# apa104-breakout.net
KiCad netlist of a schematic drawn in EAGLE
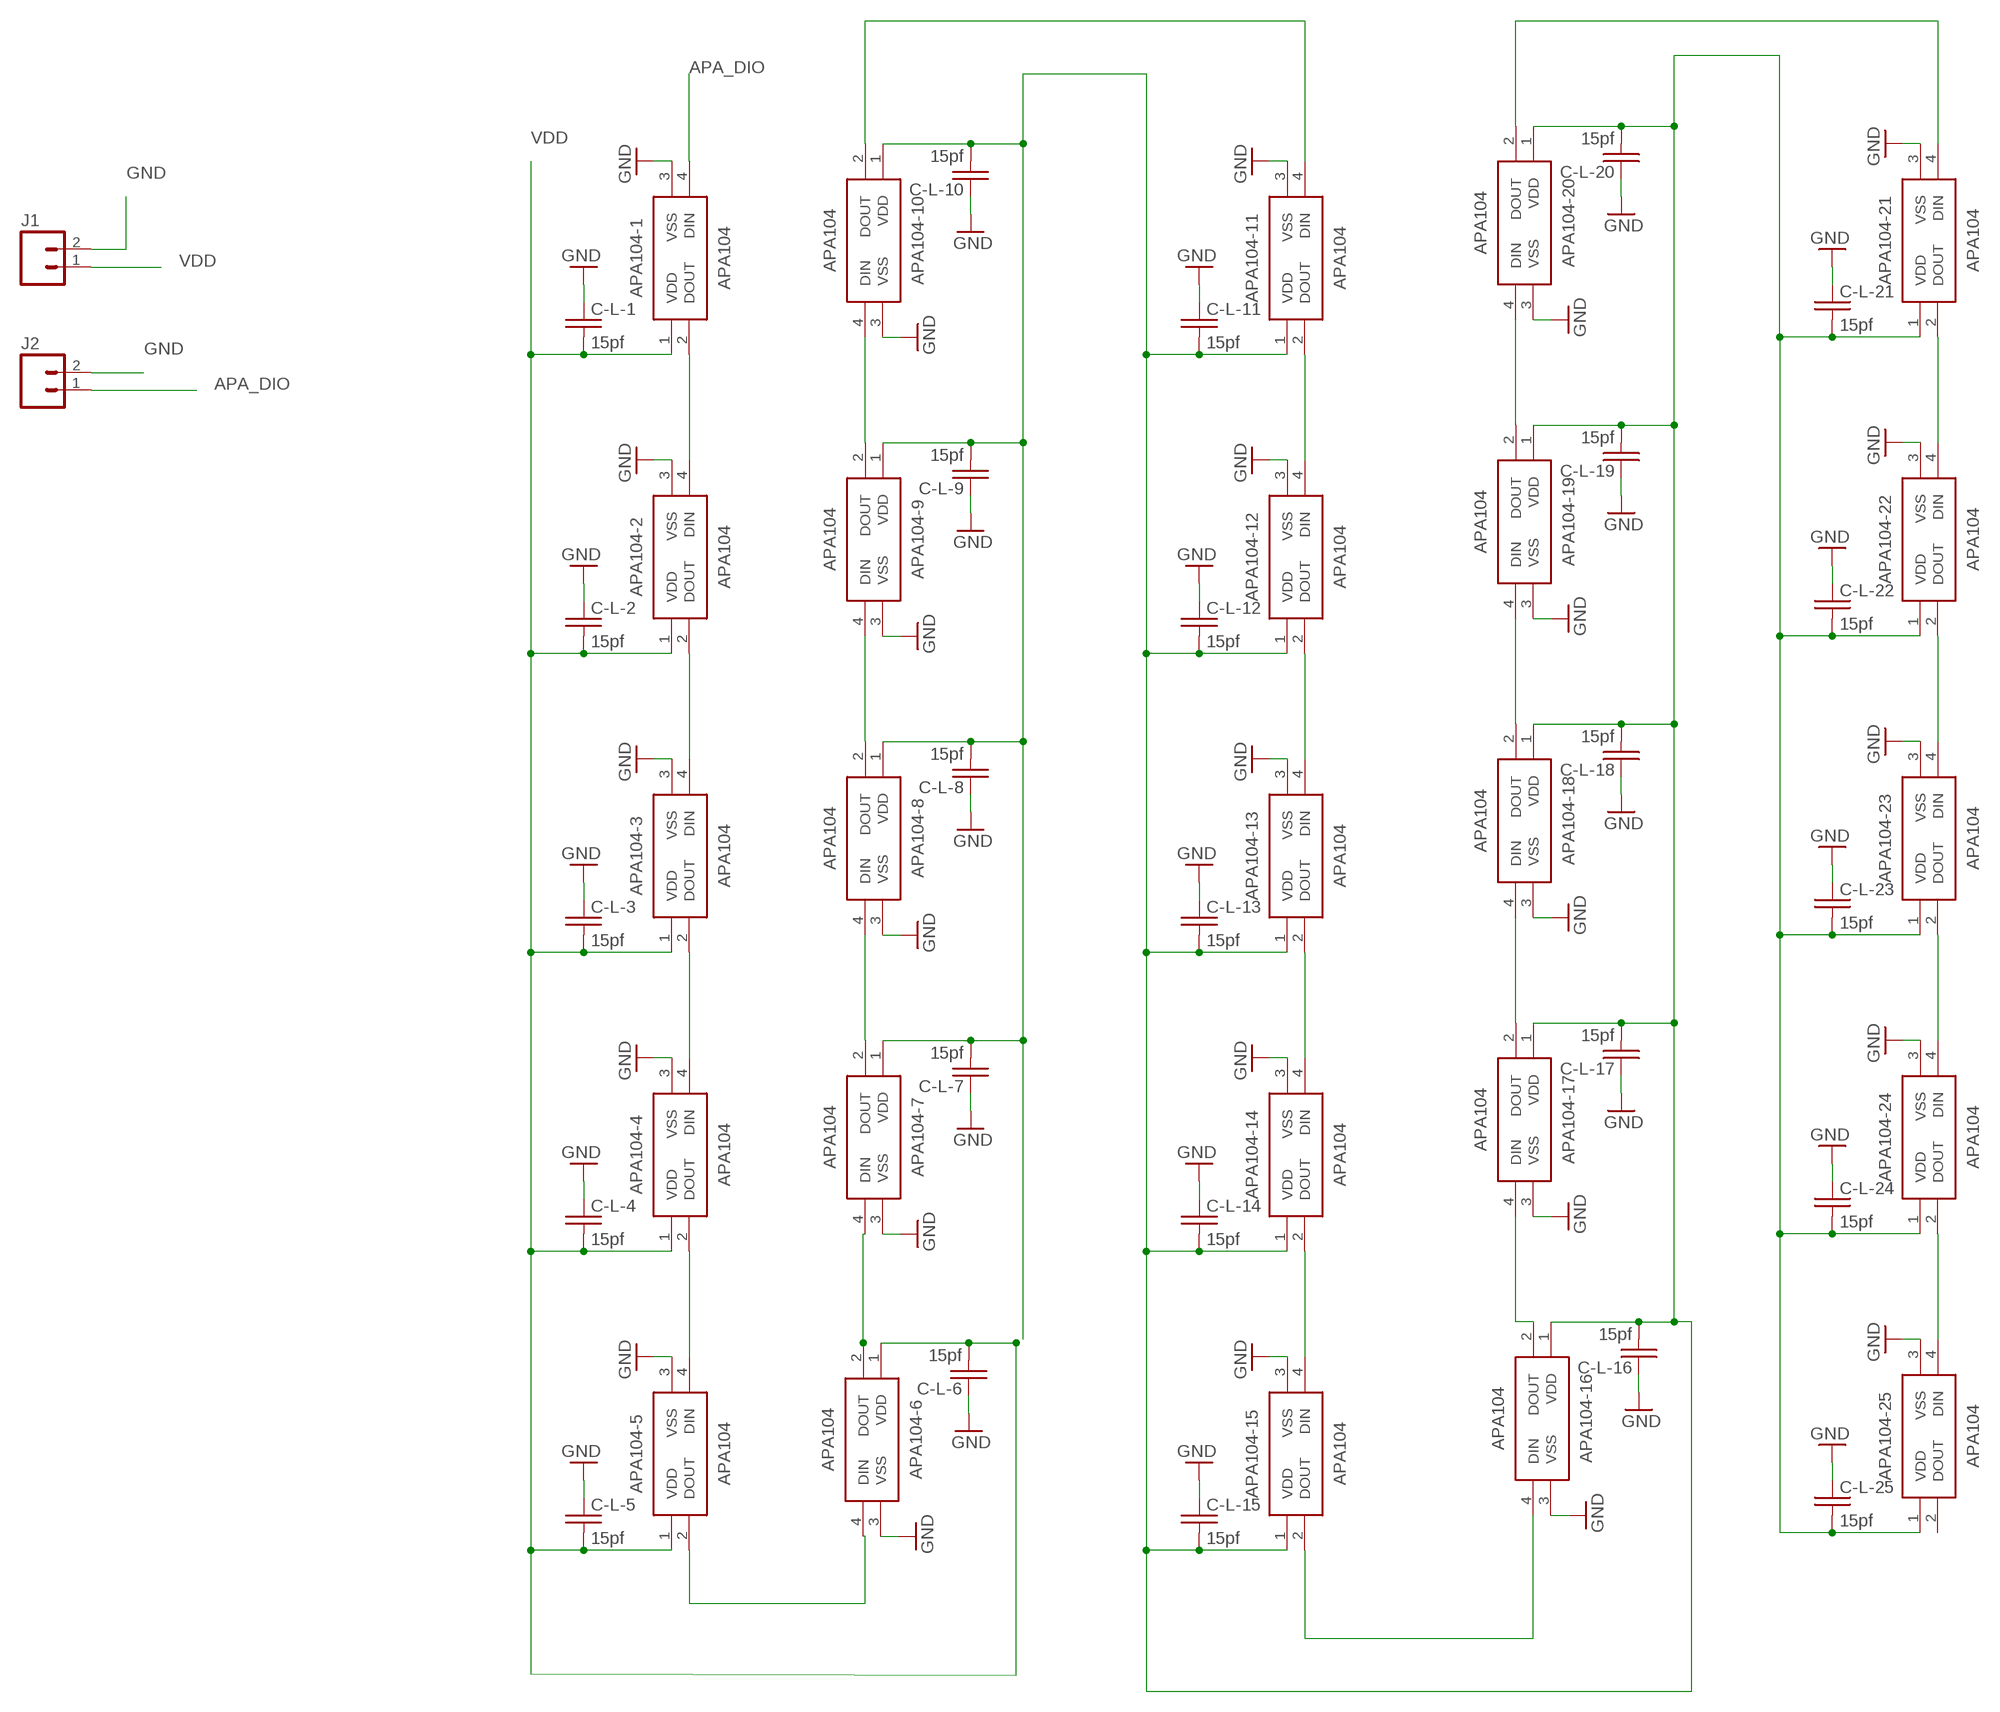
[diagram p0: schematic, sheet 1]

(export (version "E")
  (design (tool "Eeschema 10.0.6"))
  (components
    (comp (ref "APA104-1")
      (value "APA104")
      (footprint "eagle-import:APA104")
      (libsource (lib "eagle-import") (part "APA104"))
    )
    (comp (ref "APA104-2")
      (value "APA104")
      (footprint "eagle-import:APA104")
      (libsource (lib "eagle-import") (part "APA104"))
    )
    (comp (ref "APA104-3")
      (value "APA104")
      (footprint "eagle-import:APA104")
      (libsource (lib "eagle-import") (part "APA104"))
    )
    (comp (ref "APA104-4")
      (value "APA104")
      (footprint "eagle-import:APA104")
      (libsource (lib "eagle-import") (part "APA104"))
    )
    (comp (ref "APA104-5")
      (value "APA104")
      (footprint "eagle-import:APA104")
      (libsource (lib "eagle-import") (part "APA104"))
    )
    (comp (ref "APA104-6")
      (value "APA104")
      (footprint "eagle-import:APA104")
      (libsource (lib "eagle-import") (part "APA104"))
    )
    (comp (ref "APA104-7")
      (value "APA104")
      (footprint "eagle-import:APA104")
      (libsource (lib "eagle-import") (part "APA104"))
    )
    (comp (ref "APA104-8")
      (value "APA104")
      (footprint "eagle-import:APA104")
      (libsource (lib "eagle-import") (part "APA104"))
    )
    (comp (ref "APA104-9")
      (value "APA104")
      (footprint "eagle-import:APA104")
      (libsource (lib "eagle-import") (part "APA104"))
    )
    (comp (ref "APA104-10")
      (value "APA104")
      (footprint "eagle-import:APA104")
      (libsource (lib "eagle-import") (part "APA104"))
    )
    (comp (ref "APA104-11")
      (value "APA104")
      (footprint "eagle-import:APA104")
      (libsource (lib "eagle-import") (part "APA104"))
    )
    (comp (ref "APA104-12")
      (value "APA104")
      (footprint "eagle-import:APA104")
      (libsource (lib "eagle-import") (part "APA104"))
    )
    (comp (ref "APA104-13")
      (value "APA104")
      (footprint "eagle-import:APA104")
      (libsource (lib "eagle-import") (part "APA104"))
    )
    (comp (ref "APA104-14")
      (value "APA104")
      (footprint "eagle-import:APA104")
      (libsource (lib "eagle-import") (part "APA104"))
    )
    (comp (ref "APA104-15")
      (value "APA104")
      (footprint "eagle-import:APA104")
      (libsource (lib "eagle-import") (part "APA104"))
    )
    (comp (ref "APA104-16")
      (value "APA104")
      (footprint "eagle-import:APA104")
      (libsource (lib "eagle-import") (part "APA104"))
    )
    (comp (ref "APA104-17")
      (value "APA104")
      (footprint "eagle-import:APA104")
      (libsource (lib "eagle-import") (part "APA104"))
    )
    (comp (ref "APA104-18")
      (value "APA104")
      (footprint "eagle-import:APA104")
      (libsource (lib "eagle-import") (part "APA104"))
    )
    (comp (ref "APA104-19")
      (value "APA104")
      (footprint "eagle-import:APA104")
      (libsource (lib "eagle-import") (part "APA104"))
    )
    (comp (ref "APA104-20")
      (value "APA104")
      (footprint "eagle-import:APA104")
      (libsource (lib "eagle-import") (part "APA104"))
    )
    (comp (ref "APA104-21")
      (value "APA104")
      (footprint "eagle-import:APA104")
      (libsource (lib "eagle-import") (part "APA104"))
    )
    (comp (ref "APA104-22")
      (value "APA104")
      (footprint "eagle-import:APA104")
      (libsource (lib "eagle-import") (part "APA104"))
    )
    (comp (ref "APA104-23")
      (value "APA104")
      (footprint "eagle-import:APA104")
      (libsource (lib "eagle-import") (part "APA104"))
    )
    (comp (ref "APA104-24")
      (value "APA104")
      (footprint "eagle-import:APA104")
      (libsource (lib "eagle-import") (part "APA104"))
    )
    (comp (ref "APA104-25")
      (value "APA104")
      (footprint "eagle-import:APA104")
      (libsource (lib "eagle-import") (part "APA104"))
    )
    (comp (ref "C-L-1")
      (value "15pf")
      (footprint "eagle-import:C0805-VOLTA")
      (libsource (lib "eagle-import") (part "C-USC0805-VOLTERA"))
    )
    (comp (ref "C-L-2")
      (value "15pf")
      (footprint "eagle-import:C0805-VOLTA")
      (libsource (lib "eagle-import") (part "C-USC0805-VOLTERA"))
    )
    (comp (ref "C-L-3")
      (value "15pf")
      (footprint "eagle-import:C0805-VOLTA")
      (libsource (lib "eagle-import") (part "C-USC0805-VOLTERA"))
    )
    (comp (ref "C-L-4")
      (value "15pf")
      (footprint "eagle-import:C0805-VOLTA")
      (libsource (lib "eagle-import") (part "C-USC0805-VOLTERA"))
    )
    (comp (ref "C-L-5")
      (value "15pf")
      (footprint "eagle-import:C0805-VOLTA")
      (libsource (lib "eagle-import") (part "C-USC0805-VOLTERA"))
    )
    (comp (ref "C-L-6")
      (value "15pf")
      (footprint "eagle-import:C0805-VOLTA")
      (libsource (lib "eagle-import") (part "C-USC0805-VOLTERA"))
    )
    (comp (ref "C-L-7")
      (value "15pf")
      (footprint "eagle-import:C0805-VOLTA")
      (libsource (lib "eagle-import") (part "C-USC0805-VOLTERA"))
    )
    (comp (ref "C-L-8")
      (value "15pf")
      (footprint "eagle-import:C0805-VOLTA")
      (libsource (lib "eagle-import") (part "C-USC0805-VOLTERA"))
    )
    (comp (ref "C-L-9")
      (value "15pf")
      (footprint "eagle-import:C0805-VOLTA")
      (libsource (lib "eagle-import") (part "C-USC0805-VOLTERA"))
    )
    (comp (ref "C-L-10")
      (value "15pf")
      (footprint "eagle-import:C0805-VOLTA")
      (libsource (lib "eagle-import") (part "C-USC0805-VOLTERA"))
    )
    (comp (ref "C-L-11")
      (value "15pf")
      (footprint "eagle-import:C0805-VOLTA")
      (libsource (lib "eagle-import") (part "C-USC0805-VOLTERA"))
    )
    (comp (ref "C-L-12")
      (value "15pf")
      (footprint "eagle-import:C0805-VOLTA")
      (libsource (lib "eagle-import") (part "C-USC0805-VOLTERA"))
    )
    (comp (ref "C-L-13")
      (value "15pf")
      (footprint "eagle-import:C0805-VOLTA")
      (libsource (lib "eagle-import") (part "C-USC0805-VOLTERA"))
    )
    (comp (ref "C-L-14")
      (value "15pf")
      (footprint "eagle-import:C0805-VOLTA")
      (libsource (lib "eagle-import") (part "C-USC0805-VOLTERA"))
    )
    (comp (ref "C-L-15")
      (value "15pf")
      (footprint "eagle-import:C0805-VOLTA")
      (libsource (lib "eagle-import") (part "C-USC0805-VOLTERA"))
    )
    (comp (ref "C-L-16")
      (value "15pf")
      (footprint "eagle-import:C0805-VOLTA")
      (libsource (lib "eagle-import") (part "C-USC0805-VOLTERA"))
    )
    (comp (ref "C-L-17")
      (value "15pf")
      (footprint "eagle-import:C0805-VOLTA")
      (libsource (lib "eagle-import") (part "C-USC0805-VOLTERA"))
    )
    (comp (ref "C-L-18")
      (value "15pf")
      (footprint "eagle-import:C0805-VOLTA")
      (libsource (lib "eagle-import") (part "C-USC0805-VOLTERA"))
    )
    (comp (ref "C-L-19")
      (value "15pf")
      (footprint "eagle-import:C0805-VOLTA")
      (libsource (lib "eagle-import") (part "C-USC0805-VOLTERA"))
    )
    (comp (ref "C-L-20")
      (value "15pf")
      (footprint "eagle-import:C0805-VOLTA")
      (libsource (lib "eagle-import") (part "C-USC0805-VOLTERA"))
    )
    (comp (ref "C-L-21")
      (value "15pf")
      (footprint "eagle-import:C0805-VOLTA")
      (libsource (lib "eagle-import") (part "C-USC0805-VOLTERA"))
    )
    (comp (ref "C-L-22")
      (value "15pf")
      (footprint "eagle-import:C0805-VOLTA")
      (libsource (lib "eagle-import") (part "C-USC0805-VOLTERA"))
    )
    (comp (ref "C-L-23")
      (value "15pf")
      (footprint "eagle-import:C0805-VOLTA")
      (libsource (lib "eagle-import") (part "C-USC0805-VOLTERA"))
    )
    (comp (ref "C-L-24")
      (value "15pf")
      (footprint "eagle-import:C0805-VOLTA")
      (libsource (lib "eagle-import") (part "C-USC0805-VOLTERA"))
    )
    (comp (ref "C-L-25")
      (value "15pf")
      (footprint "eagle-import:C0805-VOLTA")
      (libsource (lib "eagle-import") (part "C-USC0805-VOLTERA"))
    )
    (comp (ref "J1")
      (value "M02PTH")
      (footprint "eagle-import:1X02")
      (libsource (lib "eagle-import") (part "M02PTH"))
    )
    (comp (ref "J2")
      (value "M02PTH")
      (footprint "eagle-import:1X02")
      (libsource (lib "eagle-import") (part "M02PTH"))
    )
  )
  (nets
    (net (code "1") (name "/APA_DIO") (class "Default")
      (node (ref "APA104-1") (pin "4") (pinfunction "DIN_4") (pintype "input"))
      (node (ref "J2") (pin "1") (pinfunction "1_1") (pintype "passive"))
    )
    (net (code "2") (name "/VDD") (class "Default")
      (node (ref "APA104-1") (pin "1") (pinfunction "VDD_1") (pintype "power_in"))
      (node (ref "APA104-10") (pin "1") (pinfunction "VDD_1") (pintype "power_in"))
      (node (ref "APA104-11") (pin "1") (pinfunction "VDD_1") (pintype "power_in"))
      (node (ref "APA104-12") (pin "1") (pinfunction "VDD_1") (pintype "power_in"))
      (node (ref "APA104-13") (pin "1") (pinfunction "VDD_1") (pintype "power_in"))
      (node (ref "APA104-14") (pin "1") (pinfunction "VDD_1") (pintype "power_in"))
      (node (ref "APA104-15") (pin "1") (pinfunction "VDD_1") (pintype "power_in"))
      (node (ref "APA104-16") (pin "1") (pinfunction "VDD_1") (pintype "power_in"))
      (node (ref "APA104-17") (pin "1") (pinfunction "VDD_1") (pintype "power_in"))
      (node (ref "APA104-18") (pin "1") (pinfunction "VDD_1") (pintype "power_in"))
      (node (ref "APA104-19") (pin "1") (pinfunction "VDD_1") (pintype "power_in"))
      (node (ref "APA104-2") (pin "1") (pinfunction "VDD_1") (pintype "power_in"))
      (node (ref "APA104-20") (pin "1") (pinfunction "VDD_1") (pintype "power_in"))
      (node (ref "APA104-21") (pin "1") (pinfunction "VDD_1") (pintype "power_in"))
      (node (ref "APA104-22") (pin "1") (pinfunction "VDD_1") (pintype "power_in"))
      (node (ref "APA104-23") (pin "1") (pinfunction "VDD_1") (pintype "power_in"))
      (node (ref "APA104-24") (pin "1") (pinfunction "VDD_1") (pintype "power_in"))
      (node (ref "APA104-25") (pin "1") (pinfunction "VDD_1") (pintype "power_in"))
      (node (ref "APA104-3") (pin "1") (pinfunction "VDD_1") (pintype "power_in"))
      (node (ref "APA104-4") (pin "1") (pinfunction "VDD_1") (pintype "power_in"))
      (node (ref "APA104-5") (pin "1") (pinfunction "VDD_1") (pintype "power_in"))
      (node (ref "APA104-6") (pin "1") (pinfunction "VDD_1") (pintype "power_in"))
      (node (ref "APA104-7") (pin "1") (pinfunction "VDD_1") (pintype "power_in"))
      (node (ref "APA104-8") (pin "1") (pinfunction "VDD_1") (pintype "power_in"))
      (node (ref "APA104-9") (pin "1") (pinfunction "VDD_1") (pintype "power_in"))
      (node (ref "C-L-1") (pin "2") (pinfunction "2_2") (pintype "passive"))
      (node (ref "C-L-10") (pin "2") (pinfunction "2_2") (pintype "passive"))
      (node (ref "C-L-11") (pin "2") (pinfunction "2_2") (pintype "passive"))
      (node (ref "C-L-12") (pin "2") (pinfunction "2_2") (pintype "passive"))
      (node (ref "C-L-13") (pin "2") (pinfunction "2_2") (pintype "passive"))
      (node (ref "C-L-14") (pin "2") (pinfunction "2_2") (pintype "passive"))
      (node (ref "C-L-15") (pin "2") (pinfunction "2_2") (pintype "passive"))
      (node (ref "C-L-16") (pin "2") (pinfunction "2_2") (pintype "passive"))
      (node (ref "C-L-17") (pin "2") (pinfunction "2_2") (pintype "passive"))
      (node (ref "C-L-18") (pin "2") (pinfunction "2_2") (pintype "passive"))
      (node (ref "C-L-19") (pin "2") (pinfunction "2_2") (pintype "passive"))
      (node (ref "C-L-2") (pin "2") (pinfunction "2_2") (pintype "passive"))
      (node (ref "C-L-20") (pin "2") (pinfunction "2_2") (pintype "passive"))
      (node (ref "C-L-21") (pin "2") (pinfunction "2_2") (pintype "passive"))
      (node (ref "C-L-22") (pin "2") (pinfunction "2_2") (pintype "passive"))
      (node (ref "C-L-23") (pin "2") (pinfunction "2_2") (pintype "passive"))
      (node (ref "C-L-24") (pin "2") (pinfunction "2_2") (pintype "passive"))
      (node (ref "C-L-25") (pin "2") (pinfunction "2_2") (pintype "passive"))
      (node (ref "C-L-3") (pin "2") (pinfunction "2_2") (pintype "passive"))
      (node (ref "C-L-4") (pin "2") (pinfunction "2_2") (pintype "passive"))
      (node (ref "C-L-5") (pin "2") (pinfunction "2_2") (pintype "passive"))
      (node (ref "C-L-6") (pin "2") (pinfunction "2_2") (pintype "passive"))
      (node (ref "C-L-7") (pin "2") (pinfunction "2_2") (pintype "passive"))
      (node (ref "C-L-8") (pin "2") (pinfunction "2_2") (pintype "passive"))
      (node (ref "C-L-9") (pin "2") (pinfunction "2_2") (pintype "passive"))
      (node (ref "J1") (pin "1") (pinfunction "1_1") (pintype "passive"))
    )
    (net (code "3") (name "GND") (class "Default")
      (node (ref "APA104-1") (pin "3") (pinfunction "VSS_3") (pintype "power_in"))
      (node (ref "APA104-10") (pin "3") (pinfunction "VSS_3") (pintype "power_in"))
      (node (ref "APA104-11") (pin "3") (pinfunction "VSS_3") (pintype "power_in"))
      (node (ref "APA104-12") (pin "3") (pinfunction "VSS_3") (pintype "power_in"))
      (node (ref "APA104-13") (pin "3") (pinfunction "VSS_3") (pintype "power_in"))
      (node (ref "APA104-14") (pin "3") (pinfunction "VSS_3") (pintype "power_in"))
      (node (ref "APA104-15") (pin "3") (pinfunction "VSS_3") (pintype "power_in"))
      (node (ref "APA104-16") (pin "3") (pinfunction "VSS_3") (pintype "power_in"))
      (node (ref "APA104-17") (pin "3") (pinfunction "VSS_3") (pintype "power_in"))
      (node (ref "APA104-18") (pin "3") (pinfunction "VSS_3") (pintype "power_in"))
      (node (ref "APA104-19") (pin "3") (pinfunction "VSS_3") (pintype "power_in"))
      (node (ref "APA104-2") (pin "3") (pinfunction "VSS_3") (pintype "power_in"))
      (node (ref "APA104-20") (pin "3") (pinfunction "VSS_3") (pintype "power_in"))
      (node (ref "APA104-21") (pin "3") (pinfunction "VSS_3") (pintype "power_in"))
      (node (ref "APA104-22") (pin "3") (pinfunction "VSS_3") (pintype "power_in"))
      (node (ref "APA104-23") (pin "3") (pinfunction "VSS_3") (pintype "power_in"))
      (node (ref "APA104-24") (pin "3") (pinfunction "VSS_3") (pintype "power_in"))
      (node (ref "APA104-25") (pin "3") (pinfunction "VSS_3") (pintype "power_in"))
      (node (ref "APA104-3") (pin "3") (pinfunction "VSS_3") (pintype "power_in"))
      (node (ref "APA104-4") (pin "3") (pinfunction "VSS_3") (pintype "power_in"))
      (node (ref "APA104-5") (pin "3") (pinfunction "VSS_3") (pintype "power_in"))
      (node (ref "APA104-6") (pin "3") (pinfunction "VSS_3") (pintype "power_in"))
      (node (ref "APA104-7") (pin "3") (pinfunction "VSS_3") (pintype "power_in"))
      (node (ref "APA104-8") (pin "3") (pinfunction "VSS_3") (pintype "power_in"))
      (node (ref "APA104-9") (pin "3") (pinfunction "VSS_3") (pintype "power_in"))
      (node (ref "C-L-1") (pin "1") (pinfunction "1_1") (pintype "passive"))
      (node (ref "C-L-10") (pin "1") (pinfunction "1_1") (pintype "passive"))
      (node (ref "C-L-11") (pin "1") (pinfunction "1_1") (pintype "passive"))
      (node (ref "C-L-12") (pin "1") (pinfunction "1_1") (pintype "passive"))
      (node (ref "C-L-13") (pin "1") (pinfunction "1_1") (pintype "passive"))
      (node (ref "C-L-14") (pin "1") (pinfunction "1_1") (pintype "passive"))
      (node (ref "C-L-15") (pin "1") (pinfunction "1_1") (pintype "passive"))
      (node (ref "C-L-16") (pin "1") (pinfunction "1_1") (pintype "passive"))
      (node (ref "C-L-17") (pin "1") (pinfunction "1_1") (pintype "passive"))
      (node (ref "C-L-18") (pin "1") (pinfunction "1_1") (pintype "passive"))
      (node (ref "C-L-19") (pin "1") (pinfunction "1_1") (pintype "passive"))
      (node (ref "C-L-2") (pin "1") (pinfunction "1_1") (pintype "passive"))
      (node (ref "C-L-20") (pin "1") (pinfunction "1_1") (pintype "passive"))
      (node (ref "C-L-21") (pin "1") (pinfunction "1_1") (pintype "passive"))
      (node (ref "C-L-22") (pin "1") (pinfunction "1_1") (pintype "passive"))
      (node (ref "C-L-23") (pin "1") (pinfunction "1_1") (pintype "passive"))
      (node (ref "C-L-24") (pin "1") (pinfunction "1_1") (pintype "passive"))
      (node (ref "C-L-25") (pin "1") (pinfunction "1_1") (pintype "passive"))
      (node (ref "C-L-3") (pin "1") (pinfunction "1_1") (pintype "passive"))
      (node (ref "C-L-4") (pin "1") (pinfunction "1_1") (pintype "passive"))
      (node (ref "C-L-5") (pin "1") (pinfunction "1_1") (pintype "passive"))
      (node (ref "C-L-6") (pin "1") (pinfunction "1_1") (pintype "passive"))
      (node (ref "C-L-7") (pin "1") (pinfunction "1_1") (pintype "passive"))
      (node (ref "C-L-8") (pin "1") (pinfunction "1_1") (pintype "passive"))
      (node (ref "C-L-9") (pin "1") (pinfunction "1_1") (pintype "passive"))
      (node (ref "J1") (pin "2") (pinfunction "2_2") (pintype "passive"))
      (node (ref "J2") (pin "2") (pinfunction "2_2") (pintype "passive"))
    )
    (net (code "4") (name "Net-(APA104-1-DOUT)") (class "Default")
      (node (ref "APA104-1") (pin "2") (pinfunction "DOUT_2") (pintype "output"))
      (node (ref "APA104-2") (pin "4") (pinfunction "DIN_4") (pintype "input"))
    )
    (net (code "5") (name "Net-(APA104-2-DOUT)") (class "Default")
      (node (ref "APA104-2") (pin "2") (pinfunction "DOUT_2") (pintype "output"))
      (node (ref "APA104-3") (pin "4") (pinfunction "DIN_4") (pintype "input"))
    )
    (net (code "6") (name "Net-(APA104-3-DOUT)") (class "Default")
      (node (ref "APA104-3") (pin "2") (pinfunction "DOUT_2") (pintype "output"))
      (node (ref "APA104-4") (pin "4") (pinfunction "DIN_4") (pintype "input"))
    )
    (net (code "7") (name "Net-(APA104-4-DOUT)") (class "Default")
      (node (ref "APA104-4") (pin "2") (pinfunction "DOUT_2") (pintype "output"))
      (node (ref "APA104-5") (pin "4") (pinfunction "DIN_4") (pintype "input"))
    )
    (net (code "8") (name "Net-(APA104-5-DOUT)") (class "Default")
      (node (ref "APA104-5") (pin "2") (pinfunction "DOUT_2") (pintype "output"))
      (node (ref "APA104-6") (pin "4") (pinfunction "DIN_4") (pintype "input"))
    )
    (net (code "9") (name "Net-(APA104-6-DOUT)") (class "Default")
      (node (ref "APA104-6") (pin "2") (pinfunction "DOUT_2") (pintype "output"))
      (node (ref "APA104-7") (pin "4") (pinfunction "DIN_4") (pintype "input"))
    )
    (net (code "10") (name "Net-(APA104-7-DOUT)") (class "Default")
      (node (ref "APA104-7") (pin "2") (pinfunction "DOUT_2") (pintype "output"))
      (node (ref "APA104-8") (pin "4") (pinfunction "DIN_4") (pintype "input"))
    )
    (net (code "11") (name "Net-(APA104-8-DOUT)") (class "Default")
      (node (ref "APA104-8") (pin "2") (pinfunction "DOUT_2") (pintype "output"))
      (node (ref "APA104-9") (pin "4") (pinfunction "DIN_4") (pintype "input"))
    )
    (net (code "12") (name "Net-(APA104-10-DIN)") (class "Default")
      (node (ref "APA104-10") (pin "4") (pinfunction "DIN_4") (pintype "input"))
      (node (ref "APA104-9") (pin "2") (pinfunction "DOUT_2") (pintype "output"))
    )
    (net (code "13") (name "Net-(APA104-10-DOUT)") (class "Default")
      (node (ref "APA104-10") (pin "2") (pinfunction "DOUT_2") (pintype "output"))
      (node (ref "APA104-11") (pin "4") (pinfunction "DIN_4") (pintype "input"))
    )
    (net (code "14") (name "Net-(APA104-11-DOUT)") (class "Default")
      (node (ref "APA104-11") (pin "2") (pinfunction "DOUT_2") (pintype "output"))
      (node (ref "APA104-12") (pin "4") (pinfunction "DIN_4") (pintype "input"))
    )
    (net (code "15") (name "Net-(APA104-12-DOUT)") (class "Default")
      (node (ref "APA104-12") (pin "2") (pinfunction "DOUT_2") (pintype "output"))
      (node (ref "APA104-13") (pin "4") (pinfunction "DIN_4") (pintype "input"))
    )
    (net (code "16") (name "Net-(APA104-13-DOUT)") (class "Default")
      (node (ref "APA104-13") (pin "2") (pinfunction "DOUT_2") (pintype "output"))
      (node (ref "APA104-14") (pin "4") (pinfunction "DIN_4") (pintype "input"))
    )
    (net (code "17") (name "Net-(APA104-14-DOUT)") (class "Default")
      (node (ref "APA104-14") (pin "2") (pinfunction "DOUT_2") (pintype "output"))
      (node (ref "APA104-15") (pin "4") (pinfunction "DIN_4") (pintype "input"))
    )
    (net (code "18") (name "Net-(APA104-15-DOUT)") (class "Default")
      (node (ref "APA104-15") (pin "2") (pinfunction "DOUT_2") (pintype "output"))
      (node (ref "APA104-16") (pin "4") (pinfunction "DIN_4") (pintype "input"))
    )
    (net (code "19") (name "Net-(APA104-16-DOUT)") (class "Default")
      (node (ref "APA104-16") (pin "2") (pinfunction "DOUT_2") (pintype "output"))
      (node (ref "APA104-17") (pin "4") (pinfunction "DIN_4") (pintype "input"))
    )
    (net (code "20") (name "Net-(APA104-17-DOUT)") (class "Default")
      (node (ref "APA104-17") (pin "2") (pinfunction "DOUT_2") (pintype "output"))
      (node (ref "APA104-18") (pin "4") (pinfunction "DIN_4") (pintype "input"))
    )
    (net (code "21") (name "Net-(APA104-18-DOUT)") (class "Default")
      (node (ref "APA104-18") (pin "2") (pinfunction "DOUT_2") (pintype "output"))
      (node (ref "APA104-19") (pin "4") (pinfunction "DIN_4") (pintype "input"))
    )
    (net (code "22") (name "Net-(APA104-19-DOUT)") (class "Default")
      (node (ref "APA104-19") (pin "2") (pinfunction "DOUT_2") (pintype "output"))
      (node (ref "APA104-20") (pin "4") (pinfunction "DIN_4") (pintype "input"))
    )
    (net (code "23") (name "Net-(APA104-20-DOUT)") (class "Default")
      (node (ref "APA104-20") (pin "2") (pinfunction "DOUT_2") (pintype "output"))
      (node (ref "APA104-21") (pin "4") (pinfunction "DIN_4") (pintype "input"))
    )
    (net (code "24") (name "Net-(APA104-21-DOUT)") (class "Default")
      (node (ref "APA104-21") (pin "2") (pinfunction "DOUT_2") (pintype "output"))
      (node (ref "APA104-22") (pin "4") (pinfunction "DIN_4") (pintype "input"))
    )
    (net (code "25") (name "Net-(APA104-22-DOUT)") (class "Default")
      (node (ref "APA104-22") (pin "2") (pinfunction "DOUT_2") (pintype "output"))
      (node (ref "APA104-23") (pin "4") (pinfunction "DIN_4") (pintype "input"))
    )
    (net (code "26") (name "Net-(APA104-23-DOUT)") (class "Default")
      (node (ref "APA104-23") (pin "2") (pinfunction "DOUT_2") (pintype "output"))
      (node (ref "APA104-24") (pin "4") (pinfunction "DIN_4") (pintype "input"))
    )
    (net (code "27") (name "Net-(APA104-24-DOUT)") (class "Default")
      (node (ref "APA104-24") (pin "2") (pinfunction "DOUT_2") (pintype "output"))
      (node (ref "APA104-25") (pin "4") (pinfunction "DIN_4") (pintype "input"))
    )
    (net (code "28") (name "unconnected-(APA104-25-DOUT-Pad2)") (class "Default")
      (node (ref "APA104-25") (pin "2") (pinfunction "DOUT_2") (pintype "output"))
    )
  )
)
